# tgs2611-c00.net
KiCad netlist of a schematic drawn in EAGLE
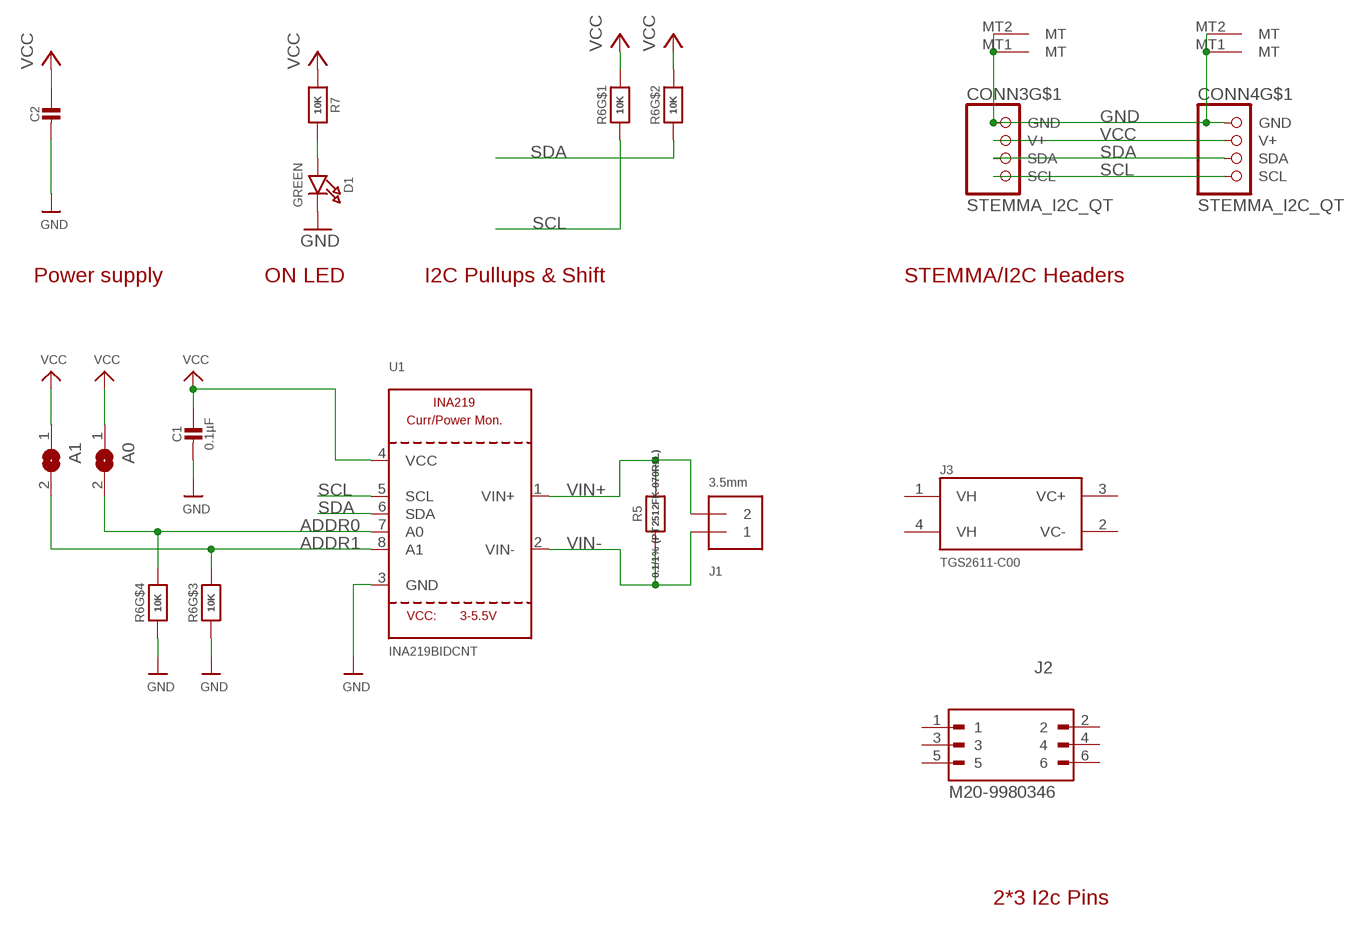
[diagram p0: schematic, sheet 1]

(export (version "E")
  (design (tool "Eeschema 10.0.6"))
  (components
    (comp (ref "A0")
      (value "SOLDERJUMPERREFLOW_NOPASTE")
      (footprint "eagle-import:SOLDERJUMPER_REFLOW_NOPASTE")
      (libsource (lib "eagle-import") (part "SOLDERJUMPERREFLOW_NOPASTE"))
    )
    (comp (ref "A1")
      (value "SOLDERJUMPERREFLOW_NOPASTE")
      (footprint "eagle-import:SOLDERJUMPER_REFLOW_NOPASTE")
      (libsource (lib "eagle-import") (part "SOLDERJUMPERREFLOW_NOPASTE"))
    )
    (comp (ref "C1")
      (value "0.1µF")
      (footprint "eagle-import:0603-NO")
      (libsource (lib "eagle-import") (part "CAP_CERAMIC0603_NO"))
    )
    (comp (ref "C2")
      (value "10uF")
      (footprint "eagle-import:0805-NO")
      (libsource (lib "eagle-import") (part "CAP_CERAMIC0805-NOOUTLINE"))
    )
    (comp (ref "CONN3")
      (value "STEMMA_I2C_QT")
      (footprint "eagle-import:JST_SH4")
      (libsource (lib "eagle-import") (part "STEMMA_I2C_QT"))
    )
    (comp (ref "CONN4")
      (value "STEMMA_I2C_QT")
      (footprint "eagle-import:JST_SH4")
      (libsource (lib "eagle-import") (part "STEMMA_I2C_QT"))
    )
    (comp (ref "D1")
      (value "GREEN")
      (footprint "eagle-import:CHIPLED_0603_NOOUTLINE")
      (libsource (lib "eagle-import") (part "LED0603_NOOUTLINE"))
    )
    (comp (ref "J1")
      (value "3.5mm")
      (footprint "eagle-import:TERMBLOCK_1X2-3.5MM")
      (libsource (lib "eagle-import") (part "TERMBLOCK_1X2_3.5MM"))
    )
    (comp (ref "J2")
      (value "M20-9980346")
      (footprint "eagle-import:HARWIN_M20-9980346")
      (fields (field (name "MANUFACTURER") "HARWIN"))
      (libsource (lib "eagle-import") (part "M20-9980346"))
    )
    (comp (ref "J3")
      (value "TGS2611-C00")
      (footprint "eagle-import:TO180P920X780-4P")
      (fields (field (name "MF") "Figaro"))
      (libsource (lib "eagle-import") (part "TGS2611-C00"))
    )
    (comp (ref "R5")
      (value "0.1/1% (PT2512FK-070R1L)")
      (footprint "eagle-import:2512")
      (libsource (lib "eagle-import") (part "RESISTOR2512"))
    )
    (comp (ref "R6")
      (value "10K")
      (footprint "eagle-import:RESPACK_4X0603")
      (libsource (lib "eagle-import") (part "RESISTOR_4PACK"))
    )
    (comp (ref "R7")
      (value "10K")
      (footprint "eagle-import:0603-NO")
      (libsource (lib "eagle-import") (part "RESISTOR_0603_NOOUT"))
    )
    (comp (ref "U1")
      (value "INA219BIDCNT")
      (footprint "eagle-import:SOT23-8")
      (libsource (lib "eagle-import") (part "INA219"))
    )
  )
  (nets
    (net (code "1") (name "/ADDR0") (class "Default")
      (node (ref "A0") (pin "2") (pinfunction "2_2") (pintype "passive"))
      (node (ref "R6") (pin "5") (pinfunction "2_5") (pintype "passive"))
      (node (ref "U1") (pin "7") (pinfunction "A0_7") (pintype "bidirectional"))
    )
    (net (code "2") (name "/ADDR1") (class "Default")
      (node (ref "A1") (pin "2") (pinfunction "2_2") (pintype "passive"))
      (node (ref "R6") (pin "6") (pinfunction "2_6") (pintype "passive"))
      (node (ref "U1") (pin "8") (pinfunction "A1_8") (pintype "bidirectional"))
    )
    (net (code "3") (name "/SCL") (class "Default")
      (node (ref "CONN3") (pin "4") (pinfunction "SCL_4") (pintype "passive"))
      (node (ref "CONN4") (pin "4") (pinfunction "SCL_4") (pintype "passive"))
      (node (ref "R6") (pin "1") (pinfunction "1_1") (pintype "passive"))
      (node (ref "U1") (pin "5") (pinfunction "SCL_5") (pintype "bidirectional"))
    )
    (net (code "4") (name "/SDA") (class "Default")
      (node (ref "CONN3") (pin "3") (pinfunction "SDA_3") (pintype "passive"))
      (node (ref "CONN4") (pin "3") (pinfunction "SDA_3") (pintype "passive"))
      (node (ref "R6") (pin "2") (pinfunction "1_2") (pintype "passive"))
      (node (ref "U1") (pin "6") (pinfunction "SDA_6") (pintype "bidirectional"))
    )
    (net (code "5") (name "/VC+") (class "Default")
      (node (ref "J3") (pin "3") (pinfunction "VC+_3") (pintype "power_in"))
    )
    (net (code "6") (name "/VC-") (class "Default")
      (node (ref "J3") (pin "2") (pinfunction "VC-_2") (pintype "power_in"))
    )
    (net (code "7") (name "/VIN+") (class "Default")
      (node (ref "J1") (pin "2") (pinfunction "2_2") (pintype "passive"))
      (node (ref "R5") (pin "2") (pinfunction "2_2") (pintype "passive"))
      (node (ref "U1") (pin "1") (pinfunction "VIN+_1") (pintype "bidirectional"))
    )
    (net (code "8") (name "/VIN-") (class "Default")
      (node (ref "J1") (pin "1") (pinfunction "1_1") (pintype "passive"))
      (node (ref "R5") (pin "1") (pinfunction "1_1") (pintype "passive"))
      (node (ref "U1") (pin "2") (pinfunction "VIN-_2") (pintype "bidirectional"))
    )
    (net (code "9") (name "GND") (class "Default")
      (node (ref "C1") (pin "2") (pinfunction "2_2") (pintype "passive"))
      (node (ref "C2") (pin "2") (pinfunction "2_2") (pintype "passive"))
      (node (ref "CONN3") (pin "1") (pinfunction "GND_1") (pintype "passive"))
      (node (ref "CONN3") (pin "MT1") (pinfunction "MT_MT1") (pintype "bidirectional"))
      (node (ref "CONN3") (pin "MT2") (pinfunction "MT_MT2") (pintype "bidirectional"))
      (node (ref "CONN4") (pin "1") (pinfunction "GND_1") (pintype "passive"))
      (node (ref "CONN4") (pin "MT1") (pinfunction "MT_MT1") (pintype "bidirectional"))
      (node (ref "CONN4") (pin "MT2") (pinfunction "MT_MT2") (pintype "bidirectional"))
      (node (ref "D1") (pin "C") (pinfunction "C_C") (pintype "passive"))
      (node (ref "R6") (pin "3") (pinfunction "1_3") (pintype "passive"))
      (node (ref "R6") (pin "4") (pinfunction "1_4") (pintype "passive"))
      (node (ref "U1") (pin "3") (pinfunction "GND_3") (pintype "power_in"))
    )
    (net (code "10") (name "Net-(D1-PadA)") (class "Default")
      (node (ref "D1") (pin "A") (pinfunction "A_A") (pintype "passive"))
      (node (ref "R7") (pin "2") (pinfunction "2_2") (pintype "passive"))
    )
    (net (code "11") (name "VCC") (class "Default")
      (node (ref "A0") (pin "1") (pinfunction "1_1") (pintype "passive"))
      (node (ref "A1") (pin "1") (pinfunction "1_1") (pintype "passive"))
      (node (ref "C1") (pin "1") (pinfunction "1_1") (pintype "passive"))
      (node (ref "C2") (pin "1") (pinfunction "1_1") (pintype "passive"))
      (node (ref "CONN3") (pin "2") (pinfunction "V+_2") (pintype "passive"))
      (node (ref "CONN4") (pin "2") (pinfunction "V+_2") (pintype "passive"))
      (node (ref "R6") (pin "7") (pinfunction "2_7") (pintype "passive"))
      (node (ref "R6") (pin "8") (pinfunction "2_8") (pintype "passive"))
      (node (ref "R7") (pin "1") (pinfunction "1_1") (pintype "passive"))
      (node (ref "U1") (pin "4") (pinfunction "VCC_4") (pintype "power_in"))
    )
    (net (code "12") (name "unconnected-(J2-Pad1)") (class "Default")
      (node (ref "J2") (pin "1") (pinfunction "1_1") (pintype "passive"))
    )
    (net (code "13") (name "unconnected-(J2-Pad2)") (class "Default")
      (node (ref "J2") (pin "2") (pinfunction "2_2") (pintype "passive"))
    )
    (net (code "14") (name "unconnected-(J2-Pad3)") (class "Default")
      (node (ref "J2") (pin "3") (pinfunction "3_3") (pintype "passive"))
    )
    (net (code "15") (name "unconnected-(J2-Pad4)") (class "Default")
      (node (ref "J2") (pin "4") (pinfunction "4_4") (pintype "passive"))
    )
    (net (code "16") (name "unconnected-(J2-Pad5)") (class "Default")
      (node (ref "J2") (pin "5") (pinfunction "5_5") (pintype "passive"))
    )
    (net (code "17") (name "unconnected-(J2-Pad6)") (class "Default")
      (node (ref "J2") (pin "6") (pinfunction "6_6") (pintype "passive"))
    )
    (net (code "18") (name "unconnected-(J3-VH-Pad1)") (class "Default")
      (node (ref "J3") (pin "1") (pinfunction "VH_1") (pintype "input"))
    )
    (net (code "19") (name "unconnected-(J3-VH-Pad4)") (class "Default")
      (node (ref "J3") (pin "4") (pinfunction "VH_4") (pintype "input"))
    )
  )
)
